# 555_mono.net
KiCad netlist of a schematic drawn in Altium Designer
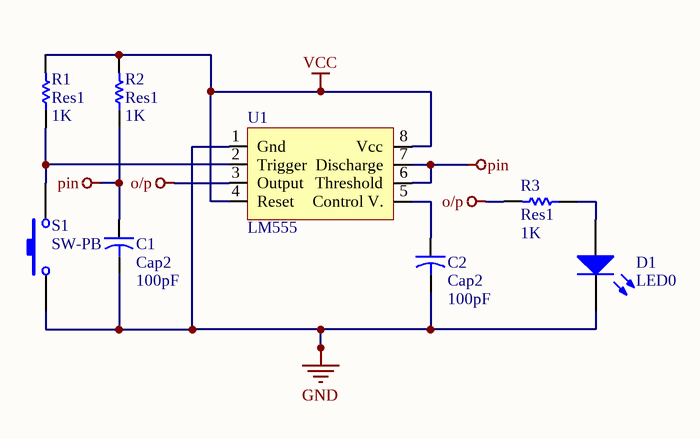
[diagram p0: 555(mono).SchDoc]

(export (version "E")
  (design (tool "Eeschema 10.0.6"))
  (components
    (comp (ref "C1")
      (value "Cap2")
      (footprint "CAPR5-4X5")
      (description "Capacitor")
      (fields (field (name "ALTIUM_VALUE") "100pF") (field (name "PUBLISHER") "Altium Limited"))
      (libsource (lib "Miscellaneous Devices") (part "Cap2"))
    )
    (comp (ref "C2")
      (value "Cap2")
      (footprint "CAPR5-4X5")
      (description "Capacitor")
      (fields (field (name "ALTIUM_VALUE") "100pF") (field (name "PUBLISHER") "Altium Limited"))
      (libsource (lib "Miscellaneous Devices") (part "Cap2"))
    )
    (comp (ref "D1")
      (value "LED0")
      (footprint "LED-0")
      (description "Typical INFRARED GaAs LED")
      (fields (field (name "PUBLISHER") "Altium Limited"))
      (libsource (lib "Miscellaneous Devices") (part "LED0"))
    )
    (comp (ref "R1")
      (value "Res1")
      (footprint "AXIAL-0.3")
      (description "Resistor")
      (fields (field (name "ALTIUM_VALUE") "1K") (field (name "PUBLISHER") "Altium Limited"))
      (libsource (lib "Miscellaneous Devices") (part "Res1"))
    )
    (comp (ref "R2")
      (value "Res1")
      (footprint "AXIAL-0.3")
      (description "Resistor")
      (fields (field (name "ALTIUM_VALUE") "1K") (field (name "PUBLISHER") "Altium Limited"))
      (libsource (lib "Miscellaneous Devices") (part "Res1"))
    )
    (comp (ref "R3")
      (value "Res1")
      (footprint "AXIAL-0.3")
      (description "Resistor")
      (fields (field (name "ALTIUM_VALUE") "1K") (field (name "PUBLISHER") "Altium Limited"))
      (libsource (lib "Miscellaneous Devices") (part "Res1"))
    )
    (comp (ref "S1")
      (value "SW-PB")
      (footprint "SPST-2")
      (description "Switch")
      (fields (field (name "PUBLISHER") "Altium Limited"))
      (libsource (lib "Miscellaneous Devices") (part "SW-PB"))
    )
    (comp (ref "U1") (value "LM555") (footprint "LM555") (libsource (lib "Schlib1") (part "LM555")))
  )
  (nets
    (net (code "1") (name "GND") (class "Default")
      (node (ref "C1") (pin "2") (pinfunction "2_2") (pintype "passive"))
      (node (ref "C2") (pin "2") (pinfunction "2_2") (pintype "passive"))
      (node (ref "D1") (pin "2") (pinfunction "K_2") (pintype "passive"))
      (node (ref "S1") (pin "1") (pinfunction "1_1") (pintype "passive"))
      (node (ref "U1") (pin "1") (pinfunction "Gnd_1") (pintype "passive"))
    )
    (net (code "2") (name "Net-(D1-A)") (class "Default")
      (node (ref "D1") (pin "1") (pinfunction "A_1") (pintype "passive"))
      (node (ref "R3") (pin "1") (pinfunction "1_1") (pintype "passive"))
    )
    (net (code "3") (name "Net-(U1-Control_V.)") (class "Default")
      (node (ref "C2") (pin "1") (pinfunction "1_1") (pintype "passive"))
      (node (ref "U1") (pin "5") (pinfunction "Control_V._5") (pintype "passive"))
    )
    (net (code "4") (name "Net-(U1-Trigger)") (class "Default")
      (node (ref "R1") (pin "1") (pinfunction "1_1") (pintype "passive"))
      (node (ref "S1") (pin "2") (pinfunction "2_2") (pintype "passive"))
      (node (ref "U1") (pin "2") (pinfunction "Trigger_2") (pintype "passive"))
    )
    (net (code "5") (name "VCC") (class "Default")
      (node (ref "R1") (pin "2") (pinfunction "2_2") (pintype "passive"))
      (node (ref "R2") (pin "2") (pinfunction "2_2") (pintype "passive"))
      (node (ref "U1") (pin "4") (pinfunction "Reset_4") (pintype "passive"))
      (node (ref "U1") (pin "8") (pinfunction "Vcc_8") (pintype "passive"))
    )
    (net (code "6") (name "o{slash}p") (class "Default")
      (node (ref "R3") (pin "2") (pinfunction "2_2") (pintype "passive"))
      (node (ref "U1") (pin "3") (pinfunction "Output_3") (pintype "passive"))
    )
    (net (code "7") (name "pin") (class "Default")
      (node (ref "C1") (pin "1") (pinfunction "1_1") (pintype "passive"))
      (node (ref "R2") (pin "1") (pinfunction "1_1") (pintype "passive"))
      (node (ref "U1") (pin "6") (pinfunction "Threshold_6") (pintype "passive"))
      (node (ref "U1") (pin "7") (pinfunction "Discharge_7") (pintype "passive"))
    )
  )
)
